# Node_1.net
KiCad netlist of a schematic drawn in EAGLE
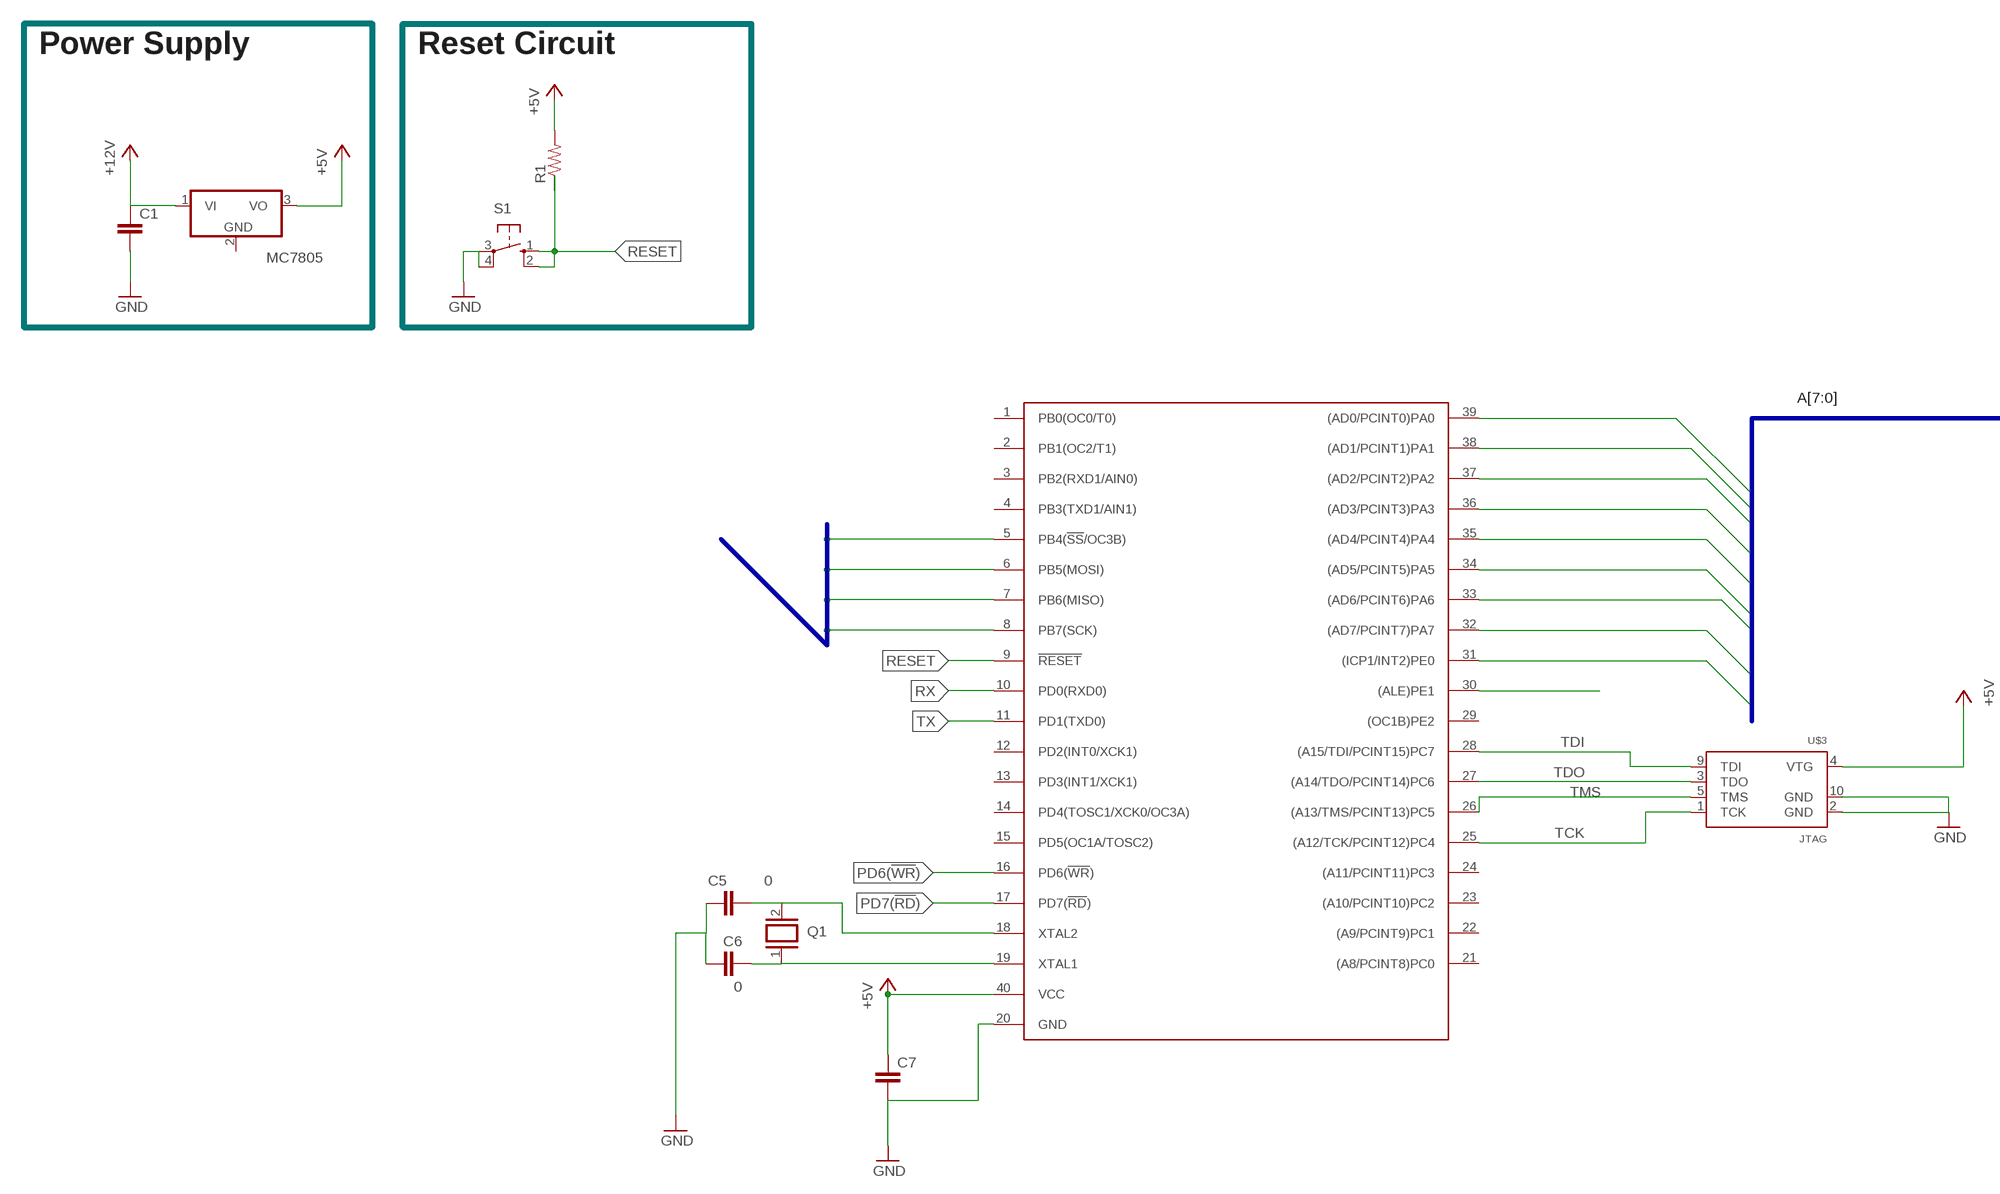
[diagram p0: schematic, sheet 1, part 1 of 2]
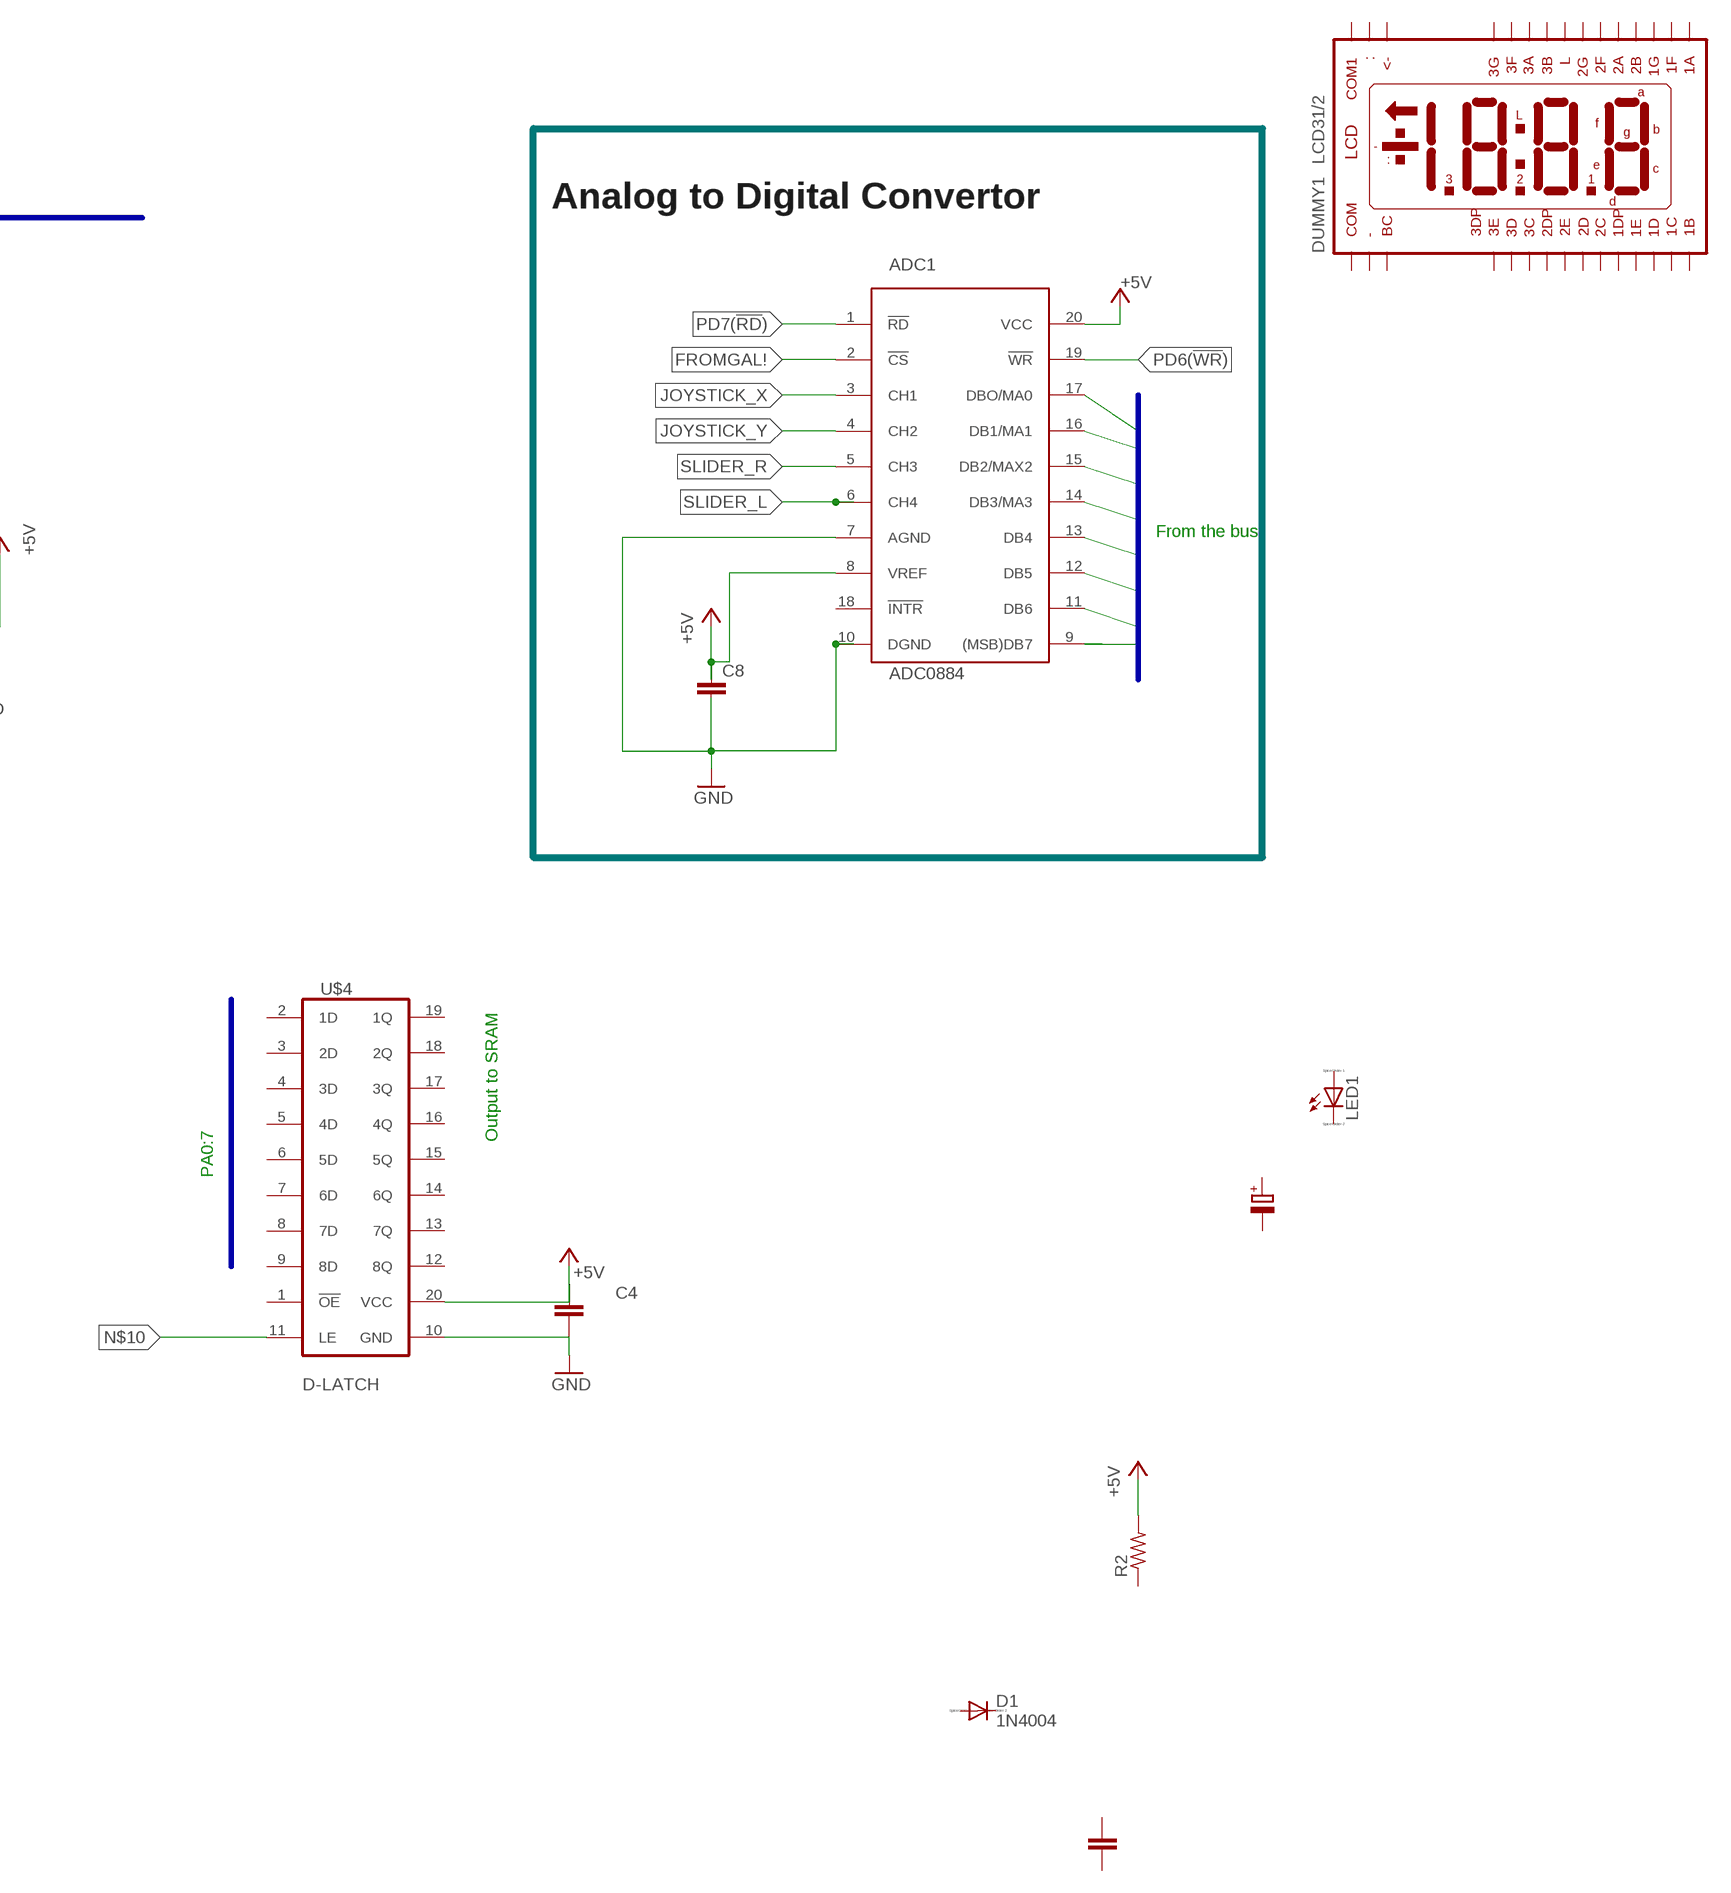
[diagram p1: schematic, sheet 1, part 2 of 2]

(export (version "E")
  (design (tool "Eeschema 10.0.6"))
  (components
    (comp (ref "ADC1")
      (value "ADC0884")
      (footprint "eagle-import:DIP")
      (libsource (lib "eagle-import") (part "ADC0884"))
    )
    (comp (ref "C1")
      (value "C-EU025-024X044")
      (footprint "eagle-import:C025-024X044")
      (libsource (lib "eagle-import") (part "resistor_C-EU025-024X044"))
    )
    (comp (ref "C4")
      (value "C-EU025-024X044")
      (footprint "eagle-import:C025-024X044")
      (libsource (lib "eagle-import") (part "resistor_C-EU025-024X044"))
    )
    (comp (ref "C5")
      (value "0")
      (footprint "eagle-import:C1206")
      (libsource (lib "eagle-import") (part "C-EUC1206"))
    )
    (comp (ref "C6")
      (value "0")
      (footprint "eagle-import:C1206")
      (libsource (lib "eagle-import") (part "C-EUC1206"))
    )
    (comp (ref "C7")
      (value "C-EU025-024X044")
      (footprint "eagle-import:C025-024X044")
      (libsource (lib "eagle-import") (part "resistor_C-EU025-024X044"))
    )
    (comp (ref "C8")
      (value "C-EU025-024X044")
      (footprint "eagle-import:C025-024X044")
      (libsource (lib "eagle-import") (part "resistor_C-EU025-024X044"))
    )
    (comp (ref "D1")
      (value "1N4004")
      (footprint "eagle-import:DO41-10")
      (libsource (lib "eagle-import") (part "1N4004"))
    )
    (comp (ref "LED1")
      (value "LED_E")
      (footprint "eagle-import:LED_1206")
      (libsource (lib "eagle-import") (part "LED_E"))
    )
    (comp (ref "Q1")
      (value "XTAL/S")
      (footprint "eagle-import:QS")
      (libsource (lib "eagle-import") (part "XTAL/S"))
    )
    (comp (ref "R1")
      (value "R-US_0204/2V")
      (footprint "eagle-import:0204V")
      (libsource (lib "eagle-import") (part "R-US_0204/2V"))
    )
    (comp (ref "R2")
      (value "R-US_0204/2V")
      (footprint "eagle-import:0204V")
      (libsource (lib "eagle-import") (part "R-US_0204/2V"))
    )
    (comp (ref "S1")
      (value "10-XX")
      (footprint "eagle-import:B3F-10XX")
      (fields (field (name "MPN") "B3F-1000"))
      (libsource (lib "eagle-import") (part "10-XX"))
    )
    (comp (ref "U$1")
      (value "ATMEGA162")
      (footprint "eagle-import:PDIP40")
      (libsource (lib "eagle-import") (part "ATMEGA162"))
    )
    (comp (ref "U$2")
      (value "MC7805")
      (footprint "eagle-import:MC7805")
      (libsource (lib "eagle-import") (part "MC7805"))
    )
    (comp (ref "U$3")
      (value "JTAG")
      (footprint "eagle-import:DIP")
      (libsource (lib "eagle-import") (part "JTAG"))
    )
    (comp (ref "U$4")
      (value "D-LATCH")
      (footprint "eagle-import:D-LATCH-20")
      (libsource (lib "eagle-import") (part "D-LATCH"))
    )
  )
  (nets
    (net (code "1") (name "+5V") (class "Default")
      (node (ref "ADC1") (pin "20") (pinfunction "VCC_20") (pintype "power_in"))
      (node (ref "ADC1") (pin "8") (pinfunction "VREF_8") (pintype "bidirectional"))
      (node (ref "C1") (pin "1") (pinfunction "1_1") (pintype "passive"))
      (node (ref "C4") (pin "1") (pinfunction "1_1") (pintype "passive"))
      (node (ref "C7") (pin "1") (pinfunction "1_1") (pintype "passive"))
      (node (ref "C8") (pin "1") (pinfunction "1_1") (pintype "passive"))
      (node (ref "R1") (pin "2") (pinfunction "2_2") (pintype "passive"))
      (node (ref "R2") (pin "2") (pinfunction "2_2") (pintype "passive"))
      (node (ref "U$1") (pin "40") (pinfunction "VCC_40") (pintype "bidirectional"))
      (node (ref "U$2") (pin "1") (pinfunction "VI_1") (pintype "input"))
      (node (ref "U$2") (pin "3") (pinfunction "VO_3") (pintype "passive"))
      (node (ref "U$3") (pin "4") (pinfunction "VTG_4") (pintype "bidirectional"))
      (node (ref "U$4") (pin "20") (pinfunction "VCC_20") (pintype "input"))
    )
    (net (code "2") (name "FROMGAL~{}") (class "Default")
      (node (ref "ADC1") (pin "2") (pinfunction "~{CS}_2") (pintype "bidirectional"))
    )
    (net (code "3") (name "GND") (class "Default")
      (node (ref "ADC1") (pin "10") (pinfunction "DGND_10") (pintype "power_in"))
      (node (ref "ADC1") (pin "7") (pinfunction "AGND_7") (pintype "bidirectional"))
      (node (ref "C1") (pin "2") (pinfunction "2_2") (pintype "passive"))
      (node (ref "C4") (pin "2") (pinfunction "2_2") (pintype "passive"))
      (node (ref "C5") (pin "1") (pinfunction "1_1") (pintype "passive"))
      (node (ref "C6") (pin "1") (pinfunction "1_1") (pintype "passive"))
      (node (ref "C7") (pin "2") (pinfunction "2_2") (pintype "passive"))
      (node (ref "C8") (pin "2") (pinfunction "2_2") (pintype "passive"))
      (node (ref "S1") (pin "3") (pinfunction "P_3") (pintype "passive"))
      (node (ref "S1") (pin "4") (pinfunction "P1_4") (pintype "passive"))
      (node (ref "U$1") (pin "20") (pinfunction "GND_20") (pintype "power_in"))
      (node (ref "U$3") (pin "10") (pinfunction "GND_10") (pintype "bidirectional"))
      (node (ref "U$3") (pin "2") (pinfunction "GND_2") (pintype "bidirectional"))
      (node (ref "U$4") (pin "10") (pinfunction "GND_10") (pintype "input"))
    )
    (net (code "4") (name "JOYSTICK_X") (class "Default")
      (node (ref "ADC1") (pin "3") (pinfunction "CH1_3") (pintype "bidirectional"))
    )
    (net (code "5") (name "JOYSTICK_Y") (class "Default")
      (node (ref "ADC1") (pin "4") (pinfunction "CH2_4") (pintype "bidirectional"))
    )
    (net (code "6") (name "N$10") (class "Default")
      (node (ref "U$4") (pin "11") (pinfunction "LE_11") (pintype "input"))
    )
    (net (code "7") (name "Net-(U$1-XTAL1)") (class "Default")
      (node (ref "C6") (pin "2") (pinfunction "2_2") (pintype "passive"))
      (node (ref "Q1") (pin "1") (pinfunction "1_1") (pintype "passive"))
      (node (ref "U$1") (pin "19") (pinfunction "XTAL1_19") (pintype "bidirectional"))
    )
    (net (code "8") (name "Net-(U$1-XTAL2)") (class "Default")
      (node (ref "C5") (pin "2") (pinfunction "2_2") (pintype "passive"))
      (node (ref "Q1") (pin "2") (pinfunction "2_2") (pintype "passive"))
      (node (ref "U$1") (pin "18") (pinfunction "XTAL2_18") (pintype "bidirectional"))
    )
    (net (code "9") (name "PD6(~{WR})") (class "Default")
      (node (ref "ADC1") (pin "19") (pinfunction "~{WR}_19") (pintype "bidirectional"))
      (node (ref "U$1") (pin "16") (pinfunction "PD6(~{WR})_16") (pintype "bidirectional"))
    )
    (net (code "10") (name "PD7(~{RD})") (class "Default")
      (node (ref "ADC1") (pin "1") (pinfunction "~{RD}_1") (pintype "bidirectional"))
      (node (ref "U$1") (pin "17") (pinfunction "PD7(~{RD})_17") (pintype "bidirectional"))
    )
    (net (code "11") (name "RESET") (class "Default")
      (node (ref "R1") (pin "1") (pinfunction "1_1") (pintype "passive"))
      (node (ref "S1") (pin "1") (pinfunction "S_1") (pintype "passive"))
      (node (ref "S1") (pin "2") (pinfunction "S1_2") (pintype "passive"))
      (node (ref "U$1") (pin "9") (pinfunction "~{RESET}_9") (pintype "bidirectional"))
    )
    (net (code "12") (name "RX") (class "Default")
      (node (ref "U$1") (pin "10") (pinfunction "PD0(RXD0)_10") (pintype "bidirectional"))
    )
    (net (code "13") (name "SLIDER_L") (class "Default")
      (node (ref "ADC1") (pin "6") (pinfunction "CH4_6") (pintype "bidirectional"))
    )
    (net (code "14") (name "SLIDER_R") (class "Default")
      (node (ref "ADC1") (pin "5") (pinfunction "CH3_5") (pintype "bidirectional"))
    )
    (net (code "15") (name "TCK") (class "Default")
      (node (ref "U$1") (pin "25") (pinfunction "(A12/TCK/PCINT12)PC4_25") (pintype "bidirectional"))
      (node (ref "U$3") (pin "1") (pinfunction "TCK_1") (pintype "bidirectional"))
    )
    (net (code "16") (name "TDI") (class "Default")
      (node (ref "U$1") (pin "28") (pinfunction "(A15/TDI/PCINT15)PC7_28") (pintype "bidirectional"))
      (node (ref "U$3") (pin "9") (pinfunction "TDI_9") (pintype "bidirectional"))
    )
    (net (code "17") (name "TDO") (class "Default")
      (node (ref "U$1") (pin "27") (pinfunction "(A14/TDO/PCINT14)PC6_27") (pintype "bidirectional"))
      (node (ref "U$3") (pin "3") (pinfunction "TDO_3") (pintype "bidirectional"))
    )
    (net (code "18") (name "TMS") (class "Default")
      (node (ref "U$1") (pin "26") (pinfunction "(A13/TMS/PCINT13)PC5_26") (pintype "bidirectional"))
      (node (ref "U$3") (pin "5") (pinfunction "TMS_5") (pintype "bidirectional"))
    )
    (net (code "19") (name "TX") (class "Default")
      (node (ref "U$1") (pin "11") (pinfunction "PD1(TXD0)_11") (pintype "bidirectional"))
    )
    (net (code "20") (name "unconnected-(ADC1-(MSB)DB7-Pad9)") (class "Default")
      (node (ref "ADC1") (pin "9") (pinfunction "(MSB)DB7_9") (pintype "bidirectional"))
    )
    (net (code "21") (name "unconnected-(ADC1-DB1{slash}MA1-Pad16)") (class "Default")
      (node (ref "ADC1") (pin "16") (pinfunction "DB1/MA1_16") (pintype "bidirectional"))
    )
    (net (code "22") (name "unconnected-(ADC1-DB2{slash}MAX2-Pad15)") (class "Default")
      (node (ref "ADC1") (pin "15") (pinfunction "DB2/MAX2_15") (pintype "bidirectional"))
    )
    (net (code "23") (name "unconnected-(ADC1-DB3{slash}MA3-Pad14)") (class "Default")
      (node (ref "ADC1") (pin "14") (pinfunction "DB3/MA3_14") (pintype "bidirectional"))
    )
    (net (code "24") (name "unconnected-(ADC1-DB4-Pad13)") (class "Default")
      (node (ref "ADC1") (pin "13") (pinfunction "DB4_13") (pintype "bidirectional"))
    )
    (net (code "25") (name "unconnected-(ADC1-DB5-Pad12)") (class "Default")
      (node (ref "ADC1") (pin "12") (pinfunction "DB5_12") (pintype "bidirectional"))
    )
    (net (code "26") (name "unconnected-(ADC1-DB6-Pad11)") (class "Default")
      (node (ref "ADC1") (pin "11") (pinfunction "DB6_11") (pintype "bidirectional"))
    )
    (net (code "27") (name "unconnected-(ADC1-DBO{slash}MA0-Pad17)") (class "Default")
      (node (ref "ADC1") (pin "17") (pinfunction "DBO/MA0_17") (pintype "bidirectional"))
    )
    (net (code "28") (name "unconnected-(ADC1-~{INTR}-Pad18)") (class "Default")
      (node (ref "ADC1") (pin "18") (pinfunction "~{INTR}_18") (pintype "bidirectional"))
    )
    (net (code "29") (name "unconnected-(D1-PadA)") (class "Default")
      (node (ref "D1") (pin "A") (pinfunction "A_A") (pintype "passive"))
    )
    (net (code "30") (name "unconnected-(D1-PadC)") (class "Default")
      (node (ref "D1") (pin "C") (pinfunction "C_C") (pintype "passive"))
    )
    (net (code "31") (name "unconnected-(LED1-PadA)") (class "Default")
      (node (ref "LED1") (pin "A") (pinfunction "A_A") (pintype "passive"))
    )
    (net (code "32") (name "unconnected-(LED1-PadC)") (class "Default")
      (node (ref "LED1") (pin "C") (pinfunction "C_C") (pintype "passive"))
    )
    (net (code "33") (name "unconnected-(R2-Pad1)") (class "Default")
      (node (ref "R2") (pin "1") (pinfunction "1_1") (pintype "passive"))
    )
    (net (code "34") (name "unconnected-(U$1-(A8{slash}PCINT8)PC0-Pad21)") (class "Default")
      (node (ref "U$1") (pin "21") (pinfunction "(A8/PCINT8)PC0_21") (pintype "bidirectional"))
    )
    (net (code "35") (name "unconnected-(U$1-(A9{slash}PCINT9)PC1-Pad22)") (class "Default")
      (node (ref "U$1") (pin "22") (pinfunction "(A9/PCINT9)PC1_22") (pintype "bidirectional"))
    )
    (net (code "36") (name "unconnected-(U$1-(A10{slash}PCINT10)PC2-Pad23)") (class "Default")
      (node (ref "U$1") (pin "23") (pinfunction "(A10/PCINT10)PC2_23") (pintype "bidirectional"))
    )
    (net (code "37") (name "unconnected-(U$1-(A11{slash}PCINT11)PC3-Pad24)") (class "Default")
      (node (ref "U$1") (pin "24") (pinfunction "(A11/PCINT11)PC3_24") (pintype "bidirectional"))
    )
    (net (code "38") (name "unconnected-(U$1-(AD0{slash}PCINT0)PA0-Pad39)") (class "Default")
      (node (ref "U$1") (pin "39") (pinfunction "(AD0/PCINT0)PA0_39") (pintype "bidirectional"))
    )
    (net (code "39") (name "unconnected-(U$1-(AD1{slash}PCINT1)PA1-Pad38)") (class "Default")
      (node (ref "U$1") (pin "38") (pinfunction "(AD1/PCINT1)PA1_38") (pintype "bidirectional"))
    )
    (net (code "40") (name "unconnected-(U$1-(AD2{slash}PCINT2)PA2-Pad37)") (class "Default")
      (node (ref "U$1") (pin "37") (pinfunction "(AD2/PCINT2)PA2_37") (pintype "bidirectional"))
    )
    (net (code "41") (name "unconnected-(U$1-(AD3{slash}PCINT3)PA3-Pad36)") (class "Default")
      (node (ref "U$1") (pin "36") (pinfunction "(AD3/PCINT3)PA3_36") (pintype "bidirectional"))
    )
    (net (code "42") (name "unconnected-(U$1-(AD4{slash}PCINT4)PA4-Pad35)") (class "Default")
      (node (ref "U$1") (pin "35") (pinfunction "(AD4/PCINT4)PA4_35") (pintype "bidirectional"))
    )
    (net (code "43") (name "unconnected-(U$1-(AD5{slash}PCINT5)PA5-Pad34)") (class "Default")
      (node (ref "U$1") (pin "34") (pinfunction "(AD5/PCINT5)PA5_34") (pintype "bidirectional"))
    )
    (net (code "44") (name "unconnected-(U$1-(AD6{slash}PCINT6)PA6-Pad33)") (class "Default")
      (node (ref "U$1") (pin "33") (pinfunction "(AD6/PCINT6)PA6_33") (pintype "bidirectional"))
    )
    (net (code "45") (name "unconnected-(U$1-(AD7{slash}PCINT7)PA7-Pad32)") (class "Default")
      (node (ref "U$1") (pin "32") (pinfunction "(AD7/PCINT7)PA7_32") (pintype "bidirectional"))
    )
    (net (code "46") (name "unconnected-(U$1-(ALE)PE1-Pad30)") (class "Default")
      (node (ref "U$1") (pin "30") (pinfunction "(ALE)PE1_30") (pintype "bidirectional"))
    )
    (net (code "47") (name "unconnected-(U$1-(ICP1{slash}INT2)PE0-Pad31)") (class "Default")
      (node (ref "U$1") (pin "31") (pinfunction "(ICP1/INT2)PE0_31") (pintype "bidirectional"))
    )
    (net (code "48") (name "unconnected-(U$1-(OC1B)PE2-Pad29)") (class "Default")
      (node (ref "U$1") (pin "29") (pinfunction "(OC1B)PE2_29") (pintype "bidirectional"))
    )
    (net (code "49") (name "unconnected-(U$1-PB0(OC0{slash}T0)-Pad1)") (class "Default")
      (node (ref "U$1") (pin "1") (pinfunction "PB0(OC0/T0)_1") (pintype "bidirectional"))
    )
    (net (code "50") (name "unconnected-(U$1-PB1(OC2{slash}T1)-Pad2)") (class "Default")
      (node (ref "U$1") (pin "2") (pinfunction "PB1(OC2/T1)_2") (pintype "bidirectional"))
    )
    (net (code "51") (name "unconnected-(U$1-PB2(RXD1{slash}AIN0)-Pad3)") (class "Default")
      (node (ref "U$1") (pin "3") (pinfunction "PB2(RXD1/AIN0)_3") (pintype "bidirectional"))
    )
    (net (code "52") (name "unconnected-(U$1-PB3(TXD1{slash}AIN1)-Pad4)") (class "Default")
      (node (ref "U$1") (pin "4") (pinfunction "PB3(TXD1/AIN1)_4") (pintype "bidirectional"))
    )
    (net (code "53") (name "unconnected-(U$1-PB4(~{SS}{slash}OC3B)-Pad5)") (class "Default")
      (node (ref "U$1") (pin "5") (pinfunction "PB4(~{SS}/OC3B)_5") (pintype "bidirectional"))
    )
    (net (code "54") (name "unconnected-(U$1-PB5(MOSI)-Pad6)") (class "Default")
      (node (ref "U$1") (pin "6") (pinfunction "PB5(MOSI)_6") (pintype "bidirectional"))
    )
    (net (code "55") (name "unconnected-(U$1-PB6(MISO)-Pad7)") (class "Default")
      (node (ref "U$1") (pin "7") (pinfunction "PB6(MISO)_7") (pintype "bidirectional"))
    )
    (net (code "56") (name "unconnected-(U$1-PB7(SCK)-Pad8)") (class "Default")
      (node (ref "U$1") (pin "8") (pinfunction "PB7(SCK)_8") (pintype "bidirectional"))
    )
    (net (code "57") (name "unconnected-(U$1-PD2(INT0{slash}XCK1)-Pad12)") (class "Default")
      (node (ref "U$1") (pin "12") (pinfunction "PD2(INT0/XCK1)_12") (pintype "bidirectional"))
    )
    (net (code "58") (name "unconnected-(U$1-PD3(INT1{slash}XCK1)-Pad13)") (class "Default")
      (node (ref "U$1") (pin "13") (pinfunction "PD3(INT1/XCK1)_13") (pintype "bidirectional"))
    )
    (net (code "59") (name "unconnected-(U$1-PD4(TOSC1{slash}XCK0{slash}OC3A)-Pad14)") (class "Default")
      (node (ref "U$1") (pin "14") (pinfunction "PD4(TOSC1/XCK0/OC3A)_14") (pintype "bidirectional"))
    )
    (net (code "60") (name "unconnected-(U$1-PD5(OC1A{slash}TOSC2)-Pad15)") (class "Default")
      (node (ref "U$1") (pin "15") (pinfunction "PD5(OC1A/TOSC2)_15") (pintype "bidirectional"))
    )
    (net (code "61") (name "unconnected-(U$2-GND-Pad2)") (class "Default")
      (node (ref "U$2") (pin "2") (pinfunction "GND_2") (pintype "passive"))
    )
    (net (code "62") (name "unconnected-(U$4-1D-Pad2)") (class "Default")
      (node (ref "U$4") (pin "2") (pinfunction "1D_2") (pintype "input"))
    )
    (net (code "63") (name "unconnected-(U$4-1Q-Pad19)") (class "Default")
      (node (ref "U$4") (pin "19") (pinfunction "1Q_19") (pintype "tri_state"))
    )
    (net (code "64") (name "unconnected-(U$4-2D-Pad3)") (class "Default")
      (node (ref "U$4") (pin "3") (pinfunction "2D_3") (pintype "input"))
    )
    (net (code "65") (name "unconnected-(U$4-2Q-Pad18)") (class "Default")
      (node (ref "U$4") (pin "18") (pinfunction "2Q_18") (pintype "tri_state"))
    )
    (net (code "66") (name "unconnected-(U$4-3D-Pad4)") (class "Default")
      (node (ref "U$4") (pin "4") (pinfunction "3D_4") (pintype "input"))
    )
    (net (code "67") (name "unconnected-(U$4-3Q-Pad17)") (class "Default")
      (node (ref "U$4") (pin "17") (pinfunction "3Q_17") (pintype "tri_state"))
    )
    (net (code "68") (name "unconnected-(U$4-4D-Pad5)") (class "Default")
      (node (ref "U$4") (pin "5") (pinfunction "4D_5") (pintype "input"))
    )
    (net (code "69") (name "unconnected-(U$4-4Q-Pad16)") (class "Default")
      (node (ref "U$4") (pin "16") (pinfunction "4Q_16") (pintype "tri_state"))
    )
    (net (code "70") (name "unconnected-(U$4-5D-Pad6)") (class "Default")
      (node (ref "U$4") (pin "6") (pinfunction "5D_6") (pintype "input"))
    )
    (net (code "71") (name "unconnected-(U$4-5Q-Pad15)") (class "Default")
      (node (ref "U$4") (pin "15") (pinfunction "5Q_15") (pintype "tri_state"))
    )
    (net (code "72") (name "unconnected-(U$4-6D-Pad7)") (class "Default")
      (node (ref "U$4") (pin "7") (pinfunction "6D_7") (pintype "input"))
    )
    (net (code "73") (name "unconnected-(U$4-6Q-Pad14)") (class "Default")
      (node (ref "U$4") (pin "14") (pinfunction "6Q_14") (pintype "tri_state"))
    )
    (net (code "74") (name "unconnected-(U$4-7D-Pad8)") (class "Default")
      (node (ref "U$4") (pin "8") (pinfunction "7D_8") (pintype "input"))
    )
    (net (code "75") (name "unconnected-(U$4-7Q-Pad13)") (class "Default")
      (node (ref "U$4") (pin "13") (pinfunction "7Q_13") (pintype "tri_state"))
    )
    (net (code "76") (name "unconnected-(U$4-8D-Pad9)") (class "Default")
      (node (ref "U$4") (pin "9") (pinfunction "8D_9") (pintype "input"))
    )
    (net (code "77") (name "unconnected-(U$4-8Q-Pad12)") (class "Default")
      (node (ref "U$4") (pin "12") (pinfunction "8Q_12") (pintype "tri_state"))
    )
    (net (code "78") (name "unconnected-(U$4-~{OE}-Pad1)") (class "Default")
      (node (ref "U$4") (pin "1") (pinfunction "~{OE}_1") (pintype "input"))
    )
  )
)
